# CoverSheet.net
KiCad netlist of a schematic drawn in Altium Designer
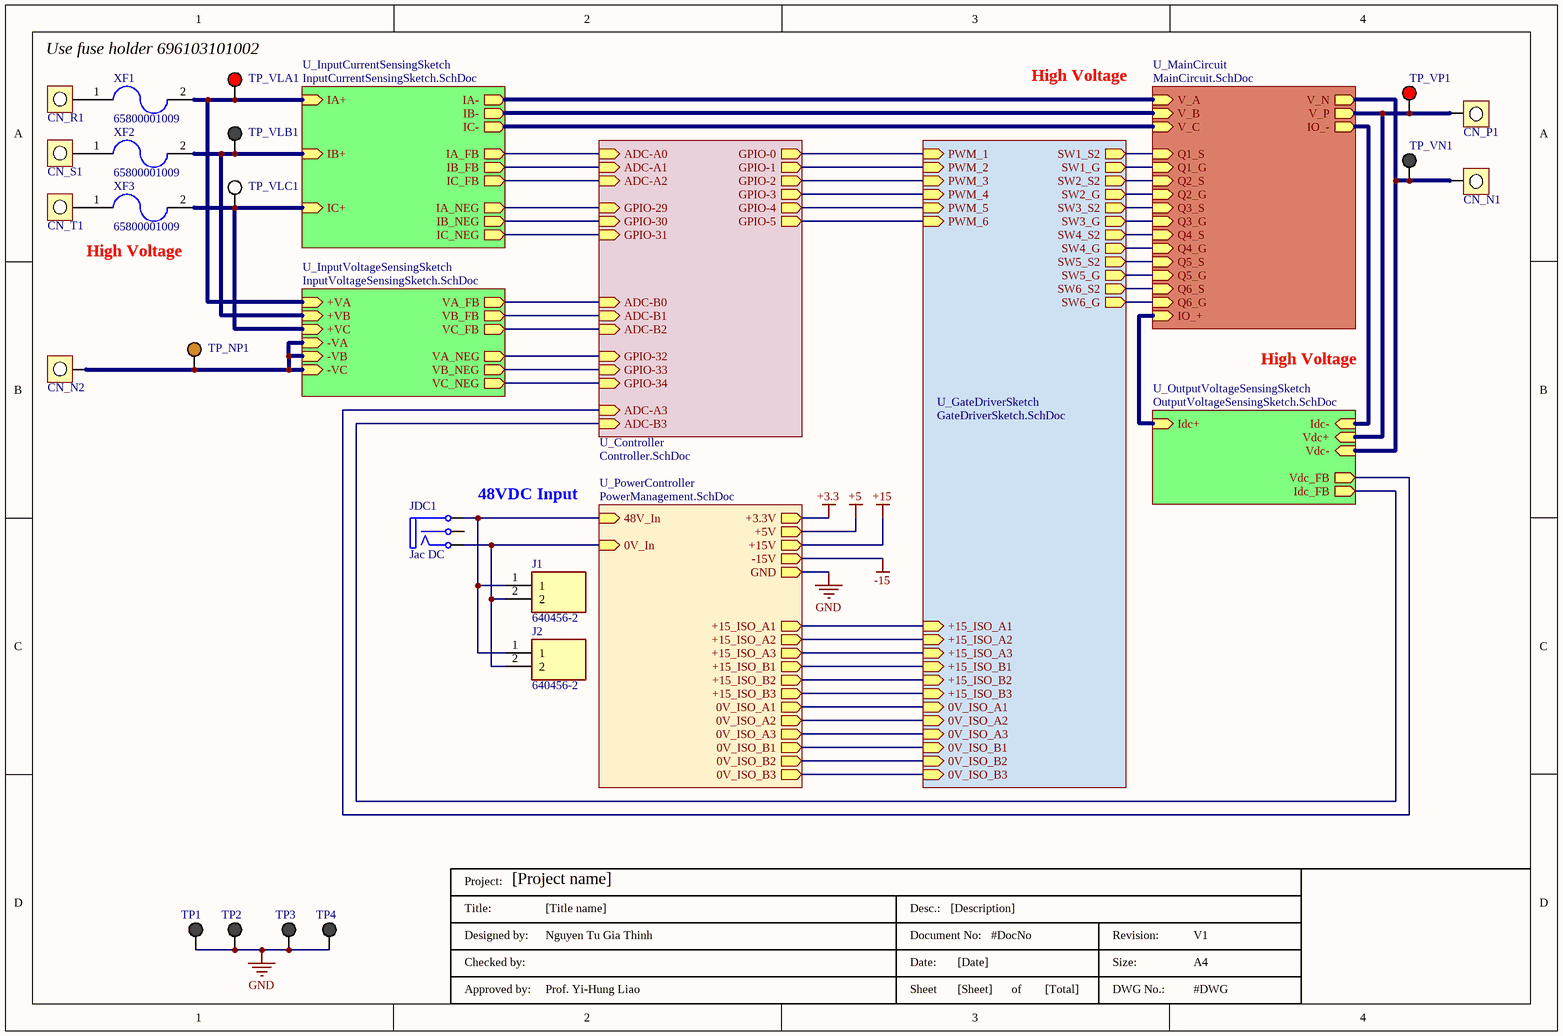
[diagram p0: CoverSheet.SchDoc]

(export (version "E")
  (design (tool "Eeschema 10.0.6"))
  (components
    (comp (ref "CN_N1")
      (value "CN")
      (footprint "P-820W")
      (description "Terminal")
      (libsource (lib "") (part "CN_1"))
    )
    (comp (ref "CN_N2")
      (value "CN")
      (footprint "P-820W")
      (description "Terminal")
      (libsource (lib "ViennaRectifier") (part "CN"))
    )
    (comp (ref "CN_P1")
      (value "CN")
      (footprint "P-820W")
      (description "Terminal")
      (libsource (lib "") (part "CN_1"))
    )
    (comp (ref "CN_R1")
      (value "CN")
      (footprint "P-820W")
      (description "Terminal")
      (libsource (lib "ViennaRectifier") (part "CN"))
    )
    (comp (ref "CN_S1")
      (value "CN")
      (footprint "P-820W")
      (description "Terminal")
      (libsource (lib "ViennaRectifier") (part "CN"))
    )
    (comp (ref "CN_T1")
      (value "CN")
      (footprint "P-820W")
      (description "Terminal")
      (libsource (lib "ViennaRectifier") (part "CN"))
    )
    (comp (ref "J1")
      (value "640456-2")
      (footprint "SamacSys:SHDR2W66P0X254_1X2_508X572X1041P")
      (description "Connector")
      (fields (field (name "MOUSER PART NUMBER") "571-6404562"))
      (libsource (lib "SamacSys") (part "640456-2"))
    )
    (comp (ref "J2")
      (value "640456-2")
      (footprint "SamacSys:SHDR2W66P0X254_1X2_508X572X1041P")
      (description "Connector")
      (fields (field (name "MOUSER PART NUMBER") "571-6404562"))
      (libsource (lib "SamacSys") (part "640456-2"))
    )
    (comp (ref "JDC1")
      (value "Jac DC")
      (footprint "DC-IN")
      (description "Jac DC input")
      (libsource (lib "ViennaRectifier") (part "DCIN"))
    )
    (comp (ref "TP1")
      (value "~")
      (footprint "5001")
      (description "Test Point Black, Multipurpose, TH")
      (libsource (lib "TestPointKeystone") (part "5001"))
    )
    (comp (ref "TP2")
      (value "~")
      (footprint "5001")
      (description "Test Point Black, Multipurpose, TH")
      (libsource (lib "TestPointKeystone") (part "5001"))
    )
    (comp (ref "TP3")
      (value "~")
      (footprint "5001")
      (description "Test Point Black, Multipurpose, TH")
      (libsource (lib "TestPointKeystone") (part "5001"))
    )
    (comp (ref "TP4")
      (value "~")
      (footprint "5001")
      (description "Test Point Black, Multipurpose, TH")
      (libsource (lib "TestPointKeystone") (part "5001"))
    )
    (comp (ref "TP_NP1")
      (value "~")
      (footprint "5003")
      (description "Test Point Orrange, Multipurpose, TH")
      (libsource (lib "TestPointKeystone") (part "5003"))
    )
    (comp (ref "TP_VLA1")
      (value "~")
      (footprint "5000")
      (description "Test Point Red, Multipurpose, TH")
      (libsource (lib "TestPointKeystone") (part "5000"))
    )
    (comp (ref "TP_VLB1")
      (value "~")
      (footprint "5001")
      (description "Test Point Black, Multipurpose, TH")
      (libsource (lib "TestPointKeystone") (part "5001"))
    )
    (comp (ref "TP_VLC1")
      (value "~")
      (footprint "5002")
      (description "Test Point White, Multipurpose, TH")
      (libsource (lib "TestPointKeystone") (part "5002"))
    )
    (comp (ref "TP_VN1")
      (value "~")
      (footprint "5001")
      (description "Test Point Black, Multipurpose, TH")
      (libsource (lib "TestPointKeystone") (part "5001"))
    )
    (comp (ref "TP_VP1")
      (value "~")
      (footprint "5000")
      (description "Test Point Red, Multipurpose, TH")
      (libsource (lib "TestPointKeystone") (part "5000"))
    )
    (comp (ref "XF1")
      (value "65800001009")
      (footprint "SamacSys:FUSM250108X1320N")
      (description "Hardware")
      (fields (field (name "MOUSER PART NUMBER") "576-65800001009"))
      (libsource (lib "ViennaRectifier") (part "65800001009"))
    )
    (comp (ref "XF2")
      (value "65800001009")
      (footprint "SamacSys:FUSM250108X1320N")
      (description "Hardware")
      (fields (field (name "MOUSER PART NUMBER") "576-65800001009"))
      (libsource (lib "ViennaRectifier") (part "65800001009"))
    )
    (comp (ref "XF3")
      (value "65800001009")
      (footprint "SamacSys:FUSM250108X1320N")
      (description "Hardware")
      (fields (field (name "MOUSER PART NUMBER") "576-65800001009"))
      (libsource (lib "ViennaRectifier") (part "65800001009"))
    )
  )
  (nets
    (net (code "11") (name "/+VA") (class "Default")
      (node (ref "TP_VLA1") (pin "1") (pinfunction "1_1") (pintype "passive"))
      (node (ref "XF1") (pin "2") (pinfunction "2_2") (pintype "passive"))
    )
    (net (code "12") (name "/+VB") (class "Default")
      (node (ref "TP_VLB1") (pin "1") (pinfunction "1_1") (pintype "passive"))
      (node (ref "XF2") (pin "2") (pinfunction "2_2") (pintype "passive"))
    )
    (net (code "13") (name "/+VC") (class "Default")
      (node (ref "TP_VLC1") (pin "1") (pinfunction "1_1") (pintype "passive"))
      (node (ref "XF3") (pin "2") (pinfunction "2_2") (pintype "passive"))
    )
    (net (code "14") (name "/-VA") (class "Default")
      (node (ref "CN_N2") (pin "1") (pinfunction "2_1") (pintype "passive"))
      (node (ref "TP_NP1") (pin "1") (pinfunction "1_1") (pintype "passive"))
    )
    (net (code "21") (name "/0V_In") (class "Default")
      (node (ref "J1") (pin "2") (pinfunction "2_2") (pintype "passive"))
      (node (ref "J2") (pin "2") (pinfunction "2_2") (pintype "passive"))
      (node (ref "JDC1") (pin "2") (pinfunction "TN_2") (pintype "passive"))
    )
    (net (code "22") (name "/48V_In") (class "Default")
      (node (ref "J1") (pin "1") (pinfunction "1_1") (pintype "passive"))
      (node (ref "J2") (pin "1") (pinfunction "1_1") (pintype "passive"))
      (node (ref "JDC1") (pin "1") (pinfunction "T_1") (pintype "passive"))
    )
    (net (code "59") (name "/V_N") (class "Default")
      (node (ref "CN_N1") (pin "1") (pinfunction "2_1") (pintype "passive"))
      (node (ref "TP_VN1") (pin "1") (pinfunction "1_1") (pintype "passive"))
    )
    (net (code "60") (name "/V_P") (class "Default")
      (node (ref "CN_P1") (pin "1") (pinfunction "2_1") (pintype "passive"))
      (node (ref "TP_VP1") (pin "1") (pinfunction "1_1") (pintype "passive"))
    )
    (net (code "62") (name "GND") (class "Default")
      (node (ref "TP1") (pin "1") (pinfunction "1_1") (pintype "passive"))
      (node (ref "TP2") (pin "1") (pinfunction "1_1") (pintype "passive"))
      (node (ref "TP3") (pin "1") (pinfunction "1_1") (pintype "passive"))
      (node (ref "TP4") (pin "1") (pinfunction "1_1") (pintype "passive"))
    )
    (net (code "63") (name "Net-(CN_R1-2)") (class "Default")
      (node (ref "CN_R1") (pin "1") (pinfunction "2_1") (pintype "passive"))
      (node (ref "XF1") (pin "1") (pinfunction "1_1") (pintype "passive"))
    )
    (net (code "64") (name "Net-(CN_S1-2)") (class "Default")
      (node (ref "CN_S1") (pin "1") (pinfunction "2_1") (pintype "passive"))
      (node (ref "XF2") (pin "1") (pinfunction "1_1") (pintype "passive"))
    )
    (net (code "65") (name "Net-(CN_T1-2)") (class "Default")
      (node (ref "CN_T1") (pin "1") (pinfunction "2_1") (pintype "passive"))
      (node (ref "XF3") (pin "1") (pinfunction "1_1") (pintype "passive"))
    )
    (net (code "66") (name "unconnected-(JDC1-S-Pad3)") (class "Default")
      (node (ref "JDC1") (pin "3") (pinfunction "S_3") (pintype "power_in"))
    )
  )
)
